# untitled.net
KiCad netlist of a schematic drawn in EAGLE
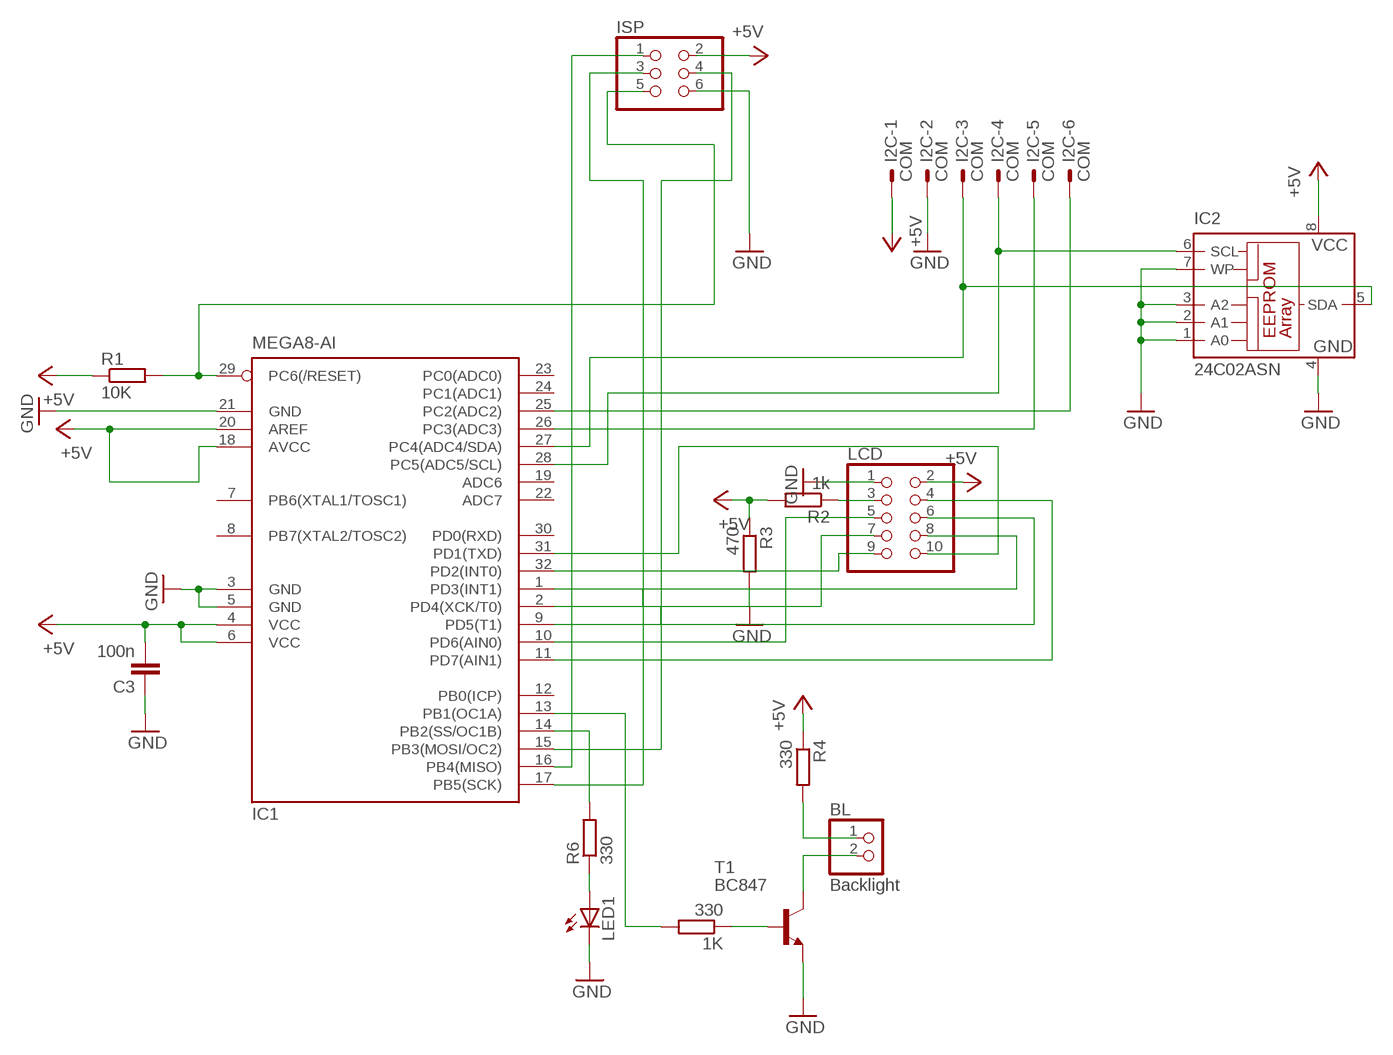
[diagram p0: schematic, sheet 1]

(export (version "E")
  (design (tool "Eeschema 10.0.6"))
  (components
    (comp (ref "1K")
      (value "330")
      (footprint "eagle-import:M0805")
      (libsource (lib "eagle-import") (part "R-EU_M0805"))
    )
    (comp (ref "BL")
      (value "Backlight")
      (footprint "eagle-import:1X02")
      (libsource (lib "eagle-import") (part "PINHD-1X2"))
    )
    (comp (ref "C3")
      (value "100n")
      (footprint "eagle-import:C0805")
      (libsource (lib "eagle-import") (part "C-EUC0805"))
    )
    (comp (ref "I2C")
      (value "COM")
      (footprint "eagle-import:ML6")
      (libsource (lib "eagle-import") (part "ML6?E"))
    )
    (comp (ref "IC1")
      (value "MEGA8-AI")
      (footprint "eagle-import:TQFP32-08")
      (libsource (lib "eagle-import") (part "MEGA8-AI"))
    )
    (comp (ref "IC2")
      (value "24C02ASN")
      (footprint "eagle-import:SO-08")
      (libsource (lib "eagle-import") (part "24CSN02A"))
    )
    (comp (ref "ISP")
      (value "PINHD-2X3")
      (footprint "eagle-import:2X03")
      (libsource (lib "eagle-import") (part "PINHD-2X3"))
    )
    (comp (ref "LCD")
      (value "PINHD-2X5")
      (footprint "eagle-import:2X05")
      (libsource (lib "eagle-import") (part "PINHD-2X5"))
    )
    (comp (ref "LED1")
      (value "LEDCHIP-LED0805")
      (footprint "eagle-import:CHIP-LED0805")
      (libsource (lib "eagle-import") (part "LEDCHIP-LED0805"))
    )
    (comp (ref "R1")
      (value "10K")
      (footprint "eagle-import:M0805")
      (libsource (lib "eagle-import") (part "R-EU_M0805"))
    )
    (comp (ref "R2")
      (value "1k")
      (footprint "eagle-import:M0805")
      (libsource (lib "eagle-import") (part "R-EU_M0805"))
    )
    (comp (ref "R3")
      (value "470")
      (footprint "eagle-import:M0805")
      (libsource (lib "eagle-import") (part "R-EU_M0805"))
    )
    (comp (ref "R4")
      (value "330")
      (footprint "eagle-import:M0805")
      (libsource (lib "eagle-import") (part "R-EU_M0805"))
    )
    (comp (ref "R6")
      (value "330")
      (footprint "eagle-import:M0805")
      (libsource (lib "eagle-import") (part "R-EU_M0805"))
    )
    (comp (ref "T1")
      (value "BC847")
      (footprint "eagle-import:SOT23")
      (libsource (lib "eagle-import") (part "BC847"))
    )
  )
  (nets
    (net (code "1") (name "+5V") (class "Default")
      (node (ref "C3") (pin "2") (pinfunction "2_2") (pintype "passive"))
      (node (ref "I2C") (pin "1") (pinfunction "S_1") (pintype "passive"))
      (node (ref "IC1") (pin "18") (pinfunction "AVCC_18") (pintype "power_in"))
      (node (ref "IC1") (pin "20") (pinfunction "AREF_20") (pintype "passive"))
      (node (ref "IC1") (pin "4") (pinfunction "VCC_4") (pintype "power_in"))
      (node (ref "IC1") (pin "6") (pinfunction "VCC_6") (pintype "power_in"))
      (node (ref "IC2") (pin "8") (pinfunction "VCC_8") (pintype "power_in"))
      (node (ref "ISP") (pin "2") (pinfunction "2_2") (pintype "passive"))
      (node (ref "LCD") (pin "2") (pinfunction "2_2") (pintype "passive"))
      (node (ref "R1") (pin "1") (pinfunction "1_1") (pintype "passive"))
      (node (ref "R2") (pin "2") (pinfunction "2_2") (pintype "passive"))
      (node (ref "R3") (pin "1") (pinfunction "1_1") (pintype "passive"))
      (node (ref "R4") (pin "1") (pinfunction "1_1") (pintype "passive"))
    )
    (net (code "2") (name "GND") (class "Default")
      (node (ref "C3") (pin "1") (pinfunction "1_1") (pintype "passive"))
      (node (ref "I2C") (pin "2") (pinfunction "S_2") (pintype "passive"))
      (node (ref "IC1") (pin "21") (pinfunction "GND_21") (pintype "power_in"))
      (node (ref "IC1") (pin "3") (pinfunction "GND_3") (pintype "power_in"))
      (node (ref "IC1") (pin "5") (pinfunction "GND_5") (pintype "power_in"))
      (node (ref "IC2") (pin "1") (pinfunction "A0_1") (pintype "input"))
      (node (ref "IC2") (pin "2") (pinfunction "A1_2") (pintype "input"))
      (node (ref "IC2") (pin "3") (pinfunction "A2_3") (pintype "input"))
      (node (ref "IC2") (pin "4") (pinfunction "GND_4") (pintype "power_in"))
      (node (ref "IC2") (pin "7") (pinfunction "WP_7") (pintype "input"))
      (node (ref "ISP") (pin "6") (pinfunction "6_6") (pintype "passive"))
      (node (ref "LCD") (pin "1") (pinfunction "1_1") (pintype "passive"))
      (node (ref "LED1") (pin "C") (pinfunction "C_C") (pintype "passive"))
      (node (ref "R3") (pin "2") (pinfunction "2_2") (pintype "passive"))
      (node (ref "T1") (pin "2") (pinfunction "E_2") (pintype "passive"))
    )
    (net (code "3") (name "Net-(BL-Pad1)") (class "Default")
      (node (ref "BL") (pin "1") (pinfunction "1_1") (pintype "passive"))
      (node (ref "R4") (pin "2") (pinfunction "2_2") (pintype "passive"))
    )
    (net (code "4") (name "Net-(I2CC-S)") (class "Default")
      (node (ref "I2C") (pin "3") (pinfunction "S_3") (pintype "passive"))
      (node (ref "IC1") (pin "27") (pinfunction "PC4(ADC4/SDA)_27") (pintype "bidirectional"))
      (node (ref "IC2") (pin "5") (pinfunction "SDA_5") (pintype "bidirectional"))
    )
    (net (code "5") (name "Net-(I2CD-S)") (class "Default")
      (node (ref "I2C") (pin "4") (pinfunction "S_4") (pintype "passive"))
      (node (ref "IC1") (pin "28") (pinfunction "PC5(ADC5/SCL)_28") (pintype "bidirectional"))
      (node (ref "IC2") (pin "6") (pinfunction "SCL_6") (pintype "input"))
    )
    (net (code "6") (name "Net-(I2CE-S)") (class "Default")
      (node (ref "I2C") (pin "5") (pinfunction "S_5") (pintype "passive"))
      (node (ref "IC1") (pin "26") (pinfunction "PC3(ADC3)_26") (pintype "bidirectional"))
    )
    (net (code "7") (name "Net-(I2CF-S)") (class "Default")
      (node (ref "I2C") (pin "6") (pinfunction "S_6") (pintype "passive"))
      (node (ref "IC1") (pin "25") (pinfunction "PC2(ADC2)_25") (pintype "bidirectional"))
    )
    (net (code "8") (name "Net-(IC1-PB1(OC1A))") (class "Default")
      (node (ref "1K") (pin "2") (pinfunction "2_2") (pintype "passive"))
      (node (ref "IC1") (pin "13") (pinfunction "PB1(OC1A)_13") (pintype "bidirectional"))
    )
    (net (code "9") (name "Net-(IC1-PB2(SS{slash}OC1B))") (class "Default")
      (node (ref "IC1") (pin "14") (pinfunction "PB2(SS/OC1B)_14") (pintype "bidirectional"))
      (node (ref "R6") (pin "2") (pinfunction "2_2") (pintype "passive"))
    )
    (net (code "10") (name "Net-(IC1-PB3(MOSI{slash}OC2))") (class "Default")
      (node (ref "IC1") (pin "15") (pinfunction "PB3(MOSI/OC2)_15") (pintype "bidirectional"))
      (node (ref "ISP") (pin "4") (pinfunction "4_4") (pintype "passive"))
    )
    (net (code "11") (name "Net-(IC1-PB4(MISO))") (class "Default")
      (node (ref "IC1") (pin "16") (pinfunction "PB4(MISO)_16") (pintype "bidirectional"))
      (node (ref "ISP") (pin "1") (pinfunction "1_1") (pintype "passive"))
    )
    (net (code "12") (name "Net-(IC1-PB5(SCK))") (class "Default")
      (node (ref "IC1") (pin "17") (pinfunction "PB5(SCK)_17") (pintype "bidirectional"))
      (node (ref "ISP") (pin "3") (pinfunction "3_3") (pintype "passive"))
    )
    (net (code "13") (name "Net-(IC1-PC6({slash}RESET))") (class "Default")
      (node (ref "IC1") (pin "29") (pinfunction "PC6(/RESET)_29") (pintype "bidirectional"))
      (node (ref "ISP") (pin "5") (pinfunction "5_5") (pintype "passive"))
      (node (ref "R1") (pin "2") (pinfunction "2_2") (pintype "passive"))
    )
    (net (code "14") (name "Net-(IC1-PD1(TXD))") (class "Default")
      (node (ref "IC1") (pin "31") (pinfunction "PD1(TXD)_31") (pintype "bidirectional"))
      (node (ref "LCD") (pin "10") (pinfunction "10_10") (pintype "passive"))
    )
    (net (code "15") (name "Net-(IC1-PD2(INT0))") (class "Default")
      (node (ref "IC1") (pin "32") (pinfunction "PD2(INT0)_32") (pintype "bidirectional"))
      (node (ref "LCD") (pin "9") (pinfunction "9_9") (pintype "passive"))
    )
    (net (code "16") (name "Net-(IC1-PD3(INT1))") (class "Default")
      (node (ref "IC1") (pin "1") (pinfunction "PD3(INT1)_1") (pintype "bidirectional"))
      (node (ref "LCD") (pin "8") (pinfunction "8_8") (pintype "passive"))
    )
    (net (code "17") (name "Net-(IC1-PD4(XCK{slash}T0))") (class "Default")
      (node (ref "IC1") (pin "2") (pinfunction "PD4(XCK/T0)_2") (pintype "bidirectional"))
      (node (ref "LCD") (pin "7") (pinfunction "7_7") (pintype "passive"))
    )
    (net (code "18") (name "Net-(IC1-PD5(T1))") (class "Default")
      (node (ref "IC1") (pin "9") (pinfunction "PD5(T1)_9") (pintype "bidirectional"))
      (node (ref "LCD") (pin "6") (pinfunction "6_6") (pintype "passive"))
    )
    (net (code "19") (name "Net-(IC1-PD6(AIN0))") (class "Default")
      (node (ref "IC1") (pin "10") (pinfunction "PD6(AIN0)_10") (pintype "bidirectional"))
      (node (ref "LCD") (pin "5") (pinfunction "5_5") (pintype "passive"))
    )
    (net (code "20") (name "Net-(IC1-PD7(AIN1))") (class "Default")
      (node (ref "IC1") (pin "11") (pinfunction "PD7(AIN1)_11") (pintype "bidirectional"))
      (node (ref "LCD") (pin "4") (pinfunction "4_4") (pintype "passive"))
    )
    (net (code "21") (name "Net-(LCD-Pad3)") (class "Default")
      (node (ref "LCD") (pin "3") (pinfunction "3_3") (pintype "passive"))
      (node (ref "R2") (pin "1") (pinfunction "1_1") (pintype "passive"))
    )
    (net (code "22") (name "Net-(LED1-PadA)") (class "Default")
      (node (ref "LED1") (pin "A") (pinfunction "A_A") (pintype "passive"))
      (node (ref "R6") (pin "1") (pinfunction "1_1") (pintype "passive"))
    )
    (net (code "23") (name "Net-(T1-B)") (class "Default")
      (node (ref "1K") (pin "1") (pinfunction "1_1") (pintype "passive"))
      (node (ref "T1") (pin "1") (pinfunction "B_1") (pintype "passive"))
    )
    (net (code "24") (name "Net-(T1-C)") (class "Default")
      (node (ref "BL") (pin "2") (pinfunction "2_2") (pintype "passive"))
      (node (ref "T1") (pin "3") (pinfunction "C_3") (pintype "passive"))
    )
    (net (code "25") (name "unconnected-(IC1-ADC6-Pad19)") (class "Default")
      (node (ref "IC1") (pin "19") (pinfunction "ADC6_19") (pintype "bidirectional"))
    )
    (net (code "26") (name "unconnected-(IC1-ADC7-Pad22)") (class "Default")
      (node (ref "IC1") (pin "22") (pinfunction "ADC7_22") (pintype "bidirectional"))
    )
    (net (code "27") (name "unconnected-(IC1-PB0(ICP)-Pad12)") (class "Default")
      (node (ref "IC1") (pin "12") (pinfunction "PB0(ICP)_12") (pintype "bidirectional"))
    )
    (net (code "28") (name "unconnected-(IC1-PB6(XTAL1{slash}TOSC1)-Pad7)") (class "Default")
      (node (ref "IC1") (pin "7") (pinfunction "PB6(XTAL1/TOSC1)_7") (pintype "bidirectional"))
    )
    (net (code "29") (name "unconnected-(IC1-PB7(XTAL2{slash}TOSC2)-Pad8)") (class "Default")
      (node (ref "IC1") (pin "8") (pinfunction "PB7(XTAL2/TOSC2)_8") (pintype "bidirectional"))
    )
    (net (code "30") (name "unconnected-(IC1-PC0(ADC0)-Pad23)") (class "Default")
      (node (ref "IC1") (pin "23") (pinfunction "PC0(ADC0)_23") (pintype "bidirectional"))
    )
    (net (code "31") (name "unconnected-(IC1-PC1(ADC1)-Pad24)") (class "Default")
      (node (ref "IC1") (pin "24") (pinfunction "PC1(ADC1)_24") (pintype "bidirectional"))
    )
    (net (code "32") (name "unconnected-(IC1-PD0(RXD)-Pad30)") (class "Default")
      (node (ref "IC1") (pin "30") (pinfunction "PD0(RXD)_30") (pintype "bidirectional"))
    )
  )
)
